# B163X.net
KiCad netlist of a schematic drawn in EAGLE
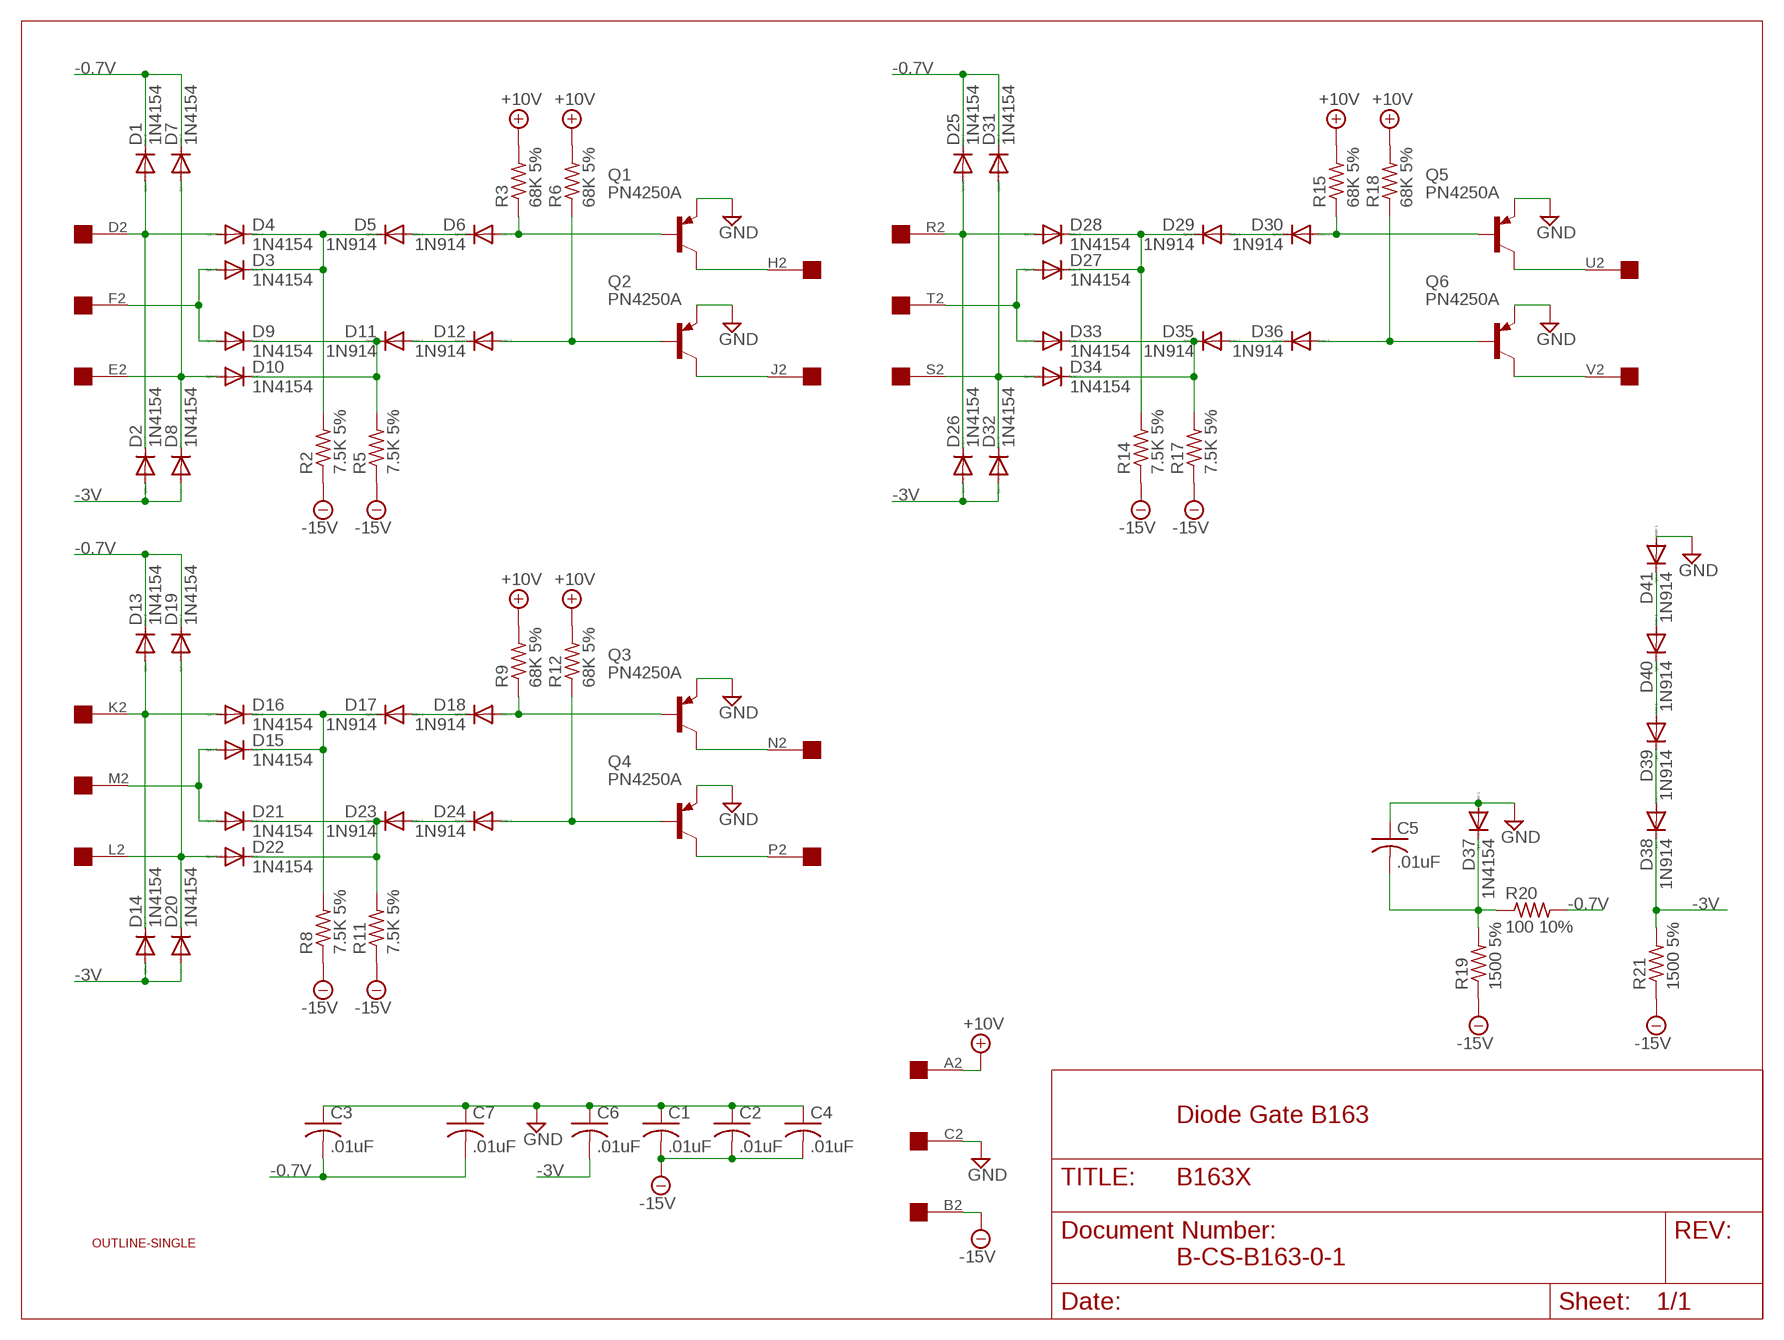
[diagram p0: schematic, sheet 1]

(export (version "E")
  (design (tool "Eeschema 10.0.6"))
  (components
    (comp (ref "C1")
      (value ".01uF")
      (footprint "eagle-import:C050-025X075")
      (libsource (lib "eagle-import") (part "C-US050-025X075"))
    )
    (comp (ref "C2")
      (value ".01uF")
      (footprint "eagle-import:C050-025X075")
      (libsource (lib "eagle-import") (part "C-US050-025X075"))
    )
    (comp (ref "C3")
      (value ".01uF")
      (footprint "eagle-import:C050-025X075")
      (libsource (lib "eagle-import") (part "C-US050-025X075"))
    )
    (comp (ref "C4")
      (value ".01uF")
      (footprint "eagle-import:C050-025X075")
      (libsource (lib "eagle-import") (part "C-US050-025X075"))
    )
    (comp (ref "C5")
      (value ".01uF")
      (footprint "eagle-import:C050-025X075")
      (libsource (lib "eagle-import") (part "C-US050-025X075"))
    )
    (comp (ref "C6")
      (value ".01uF")
      (footprint "eagle-import:C050-025X075")
      (libsource (lib "eagle-import") (part "C-US050-025X075"))
    )
    (comp (ref "C7")
      (value ".01uF")
      (footprint "eagle-import:C050-025X075")
      (libsource (lib "eagle-import") (part "C-US050-025X075"))
    )
    (comp (ref "D1")
      (value "1N4154")
      (footprint "eagle-import:DO35-10")
      (libsource (lib "eagle-import") (part "1N4148DO35-10"))
    )
    (comp (ref "D2")
      (value "1N4154")
      (footprint "eagle-import:DO35-10")
      (libsource (lib "eagle-import") (part "1N4148DO35-10"))
    )
    (comp (ref "D3")
      (value "1N4154")
      (footprint "eagle-import:DO35-10")
      (libsource (lib "eagle-import") (part "1N4148DO35-10"))
    )
    (comp (ref "D4")
      (value "1N4154")
      (footprint "eagle-import:DO35-10")
      (libsource (lib "eagle-import") (part "1N4148DO35-10"))
    )
    (comp (ref "D5")
      (value "1N914")
      (footprint "eagle-import:DO35-10")
      (libsource (lib "eagle-import") (part "1N4148DO35-10"))
    )
    (comp (ref "D6")
      (value "1N914")
      (footprint "eagle-import:DO35-10")
      (libsource (lib "eagle-import") (part "1N4148DO35-10"))
    )
    (comp (ref "D7")
      (value "1N4154")
      (footprint "eagle-import:DO35-10")
      (libsource (lib "eagle-import") (part "1N4148DO35-10"))
    )
    (comp (ref "D8")
      (value "1N4154")
      (footprint "eagle-import:DO35-10")
      (libsource (lib "eagle-import") (part "1N4148DO35-10"))
    )
    (comp (ref "D9")
      (value "1N4154")
      (footprint "eagle-import:DO35-10")
      (libsource (lib "eagle-import") (part "1N4148DO35-10"))
    )
    (comp (ref "D10")
      (value "1N4154")
      (footprint "eagle-import:DO35-10")
      (libsource (lib "eagle-import") (part "1N4148DO35-10"))
    )
    (comp (ref "D11")
      (value "1N914")
      (footprint "eagle-import:DO35-10")
      (libsource (lib "eagle-import") (part "1N4148DO35-10"))
    )
    (comp (ref "D12")
      (value "1N914")
      (footprint "eagle-import:DO35-10")
      (libsource (lib "eagle-import") (part "1N4148DO35-10"))
    )
    (comp (ref "D13")
      (value "1N4154")
      (footprint "eagle-import:DO35-10")
      (libsource (lib "eagle-import") (part "1N4148DO35-10"))
    )
    (comp (ref "D14")
      (value "1N4154")
      (footprint "eagle-import:DO35-10")
      (libsource (lib "eagle-import") (part "1N4148DO35-10"))
    )
    (comp (ref "D15")
      (value "1N4154")
      (footprint "eagle-import:DO35-10")
      (libsource (lib "eagle-import") (part "1N4148DO35-10"))
    )
    (comp (ref "D16")
      (value "1N4154")
      (footprint "eagle-import:DO35-10")
      (libsource (lib "eagle-import") (part "1N4148DO35-10"))
    )
    (comp (ref "D17")
      (value "1N914")
      (footprint "eagle-import:DO35-10")
      (libsource (lib "eagle-import") (part "1N4148DO35-10"))
    )
    (comp (ref "D18")
      (value "1N914")
      (footprint "eagle-import:DO35-10")
      (libsource (lib "eagle-import") (part "1N4148DO35-10"))
    )
    (comp (ref "D19")
      (value "1N4154")
      (footprint "eagle-import:DO35-10")
      (libsource (lib "eagle-import") (part "1N4148DO35-10"))
    )
    (comp (ref "D20")
      (value "1N4154")
      (footprint "eagle-import:DO35-10")
      (libsource (lib "eagle-import") (part "1N4148DO35-10"))
    )
    (comp (ref "D21")
      (value "1N4154")
      (footprint "eagle-import:DO35-10")
      (libsource (lib "eagle-import") (part "1N4148DO35-10"))
    )
    (comp (ref "D22")
      (value "1N4154")
      (footprint "eagle-import:DO35-10")
      (libsource (lib "eagle-import") (part "1N4148DO35-10"))
    )
    (comp (ref "D23")
      (value "1N914")
      (footprint "eagle-import:DO35-10")
      (libsource (lib "eagle-import") (part "1N4148DO35-10"))
    )
    (comp (ref "D24")
      (value "1N914")
      (footprint "eagle-import:DO35-10")
      (libsource (lib "eagle-import") (part "1N4148DO35-10"))
    )
    (comp (ref "D25")
      (value "1N4154")
      (footprint "eagle-import:DO35-10")
      (libsource (lib "eagle-import") (part "1N4148DO35-10"))
    )
    (comp (ref "D26")
      (value "1N4154")
      (footprint "eagle-import:DO35-10")
      (libsource (lib "eagle-import") (part "1N4148DO35-10"))
    )
    (comp (ref "D27")
      (value "1N4154")
      (footprint "eagle-import:DO35-10")
      (libsource (lib "eagle-import") (part "1N4148DO35-10"))
    )
    (comp (ref "D28")
      (value "1N4154")
      (footprint "eagle-import:DO35-10")
      (libsource (lib "eagle-import") (part "1N4148DO35-10"))
    )
    (comp (ref "D29")
      (value "1N914")
      (footprint "eagle-import:DO35-10")
      (libsource (lib "eagle-import") (part "1N4148DO35-10"))
    )
    (comp (ref "D30")
      (value "1N914")
      (footprint "eagle-import:DO35-10")
      (libsource (lib "eagle-import") (part "1N4148DO35-10"))
    )
    (comp (ref "D31")
      (value "1N4154")
      (footprint "eagle-import:DO35-10")
      (libsource (lib "eagle-import") (part "1N4148DO35-10"))
    )
    (comp (ref "D32")
      (value "1N4154")
      (footprint "eagle-import:DO35-10")
      (libsource (lib "eagle-import") (part "1N4148DO35-10"))
    )
    (comp (ref "D33")
      (value "1N4154")
      (footprint "eagle-import:DO35-10")
      (libsource (lib "eagle-import") (part "1N4148DO35-10"))
    )
    (comp (ref "D34")
      (value "1N4154")
      (footprint "eagle-import:DO35-10")
      (libsource (lib "eagle-import") (part "1N4148DO35-10"))
    )
    (comp (ref "D35")
      (value "1N914")
      (footprint "eagle-import:DO35-10")
      (libsource (lib "eagle-import") (part "1N4148DO35-10"))
    )
    (comp (ref "D36")
      (value "1N914")
      (footprint "eagle-import:DO35-10")
      (libsource (lib "eagle-import") (part "1N4148DO35-10"))
    )
    (comp (ref "D37")
      (value "1N4154")
      (footprint "eagle-import:DO35-10")
      (libsource (lib "eagle-import") (part "1N4148DO35-10"))
    )
    (comp (ref "D38")
      (value "1N914")
      (footprint "eagle-import:DO35-10")
      (libsource (lib "eagle-import") (part "1N4148DO35-10"))
    )
    (comp (ref "D39")
      (value "1N914")
      (footprint "eagle-import:DO35-10")
      (libsource (lib "eagle-import") (part "1N4148DO35-10"))
    )
    (comp (ref "D40")
      (value "1N914")
      (footprint "eagle-import:DO35-10")
      (libsource (lib "eagle-import") (part "1N4148DO35-10"))
    )
    (comp (ref "D41")
      (value "1N914")
      (footprint "eagle-import:DO35-10")
      (libsource (lib "eagle-import") (part "1N4148DO35-10"))
    )
    (comp (ref "Q1")
      (value "PN4250A")
      (footprint "eagle-import:TO39")
      (libsource (lib "eagle-import") (part "2N2904"))
    )
    (comp (ref "Q2")
      (value "PN4250A")
      (footprint "eagle-import:TO39")
      (libsource (lib "eagle-import") (part "2N2904"))
    )
    (comp (ref "Q3")
      (value "PN4250A")
      (footprint "eagle-import:TO39")
      (libsource (lib "eagle-import") (part "2N2904"))
    )
    (comp (ref "Q4")
      (value "PN4250A")
      (footprint "eagle-import:TO39")
      (libsource (lib "eagle-import") (part "2N2904"))
    )
    (comp (ref "Q5")
      (value "PN4250A")
      (footprint "eagle-import:TO39")
      (libsource (lib "eagle-import") (part "2N2904"))
    )
    (comp (ref "Q6")
      (value "PN4250A")
      (footprint "eagle-import:TO39")
      (libsource (lib "eagle-import") (part "2N2904"))
    )
    (comp (ref "R2")
      (value "7.5K 5%")
      (footprint "eagle-import:0207_10")
      (libsource (lib "eagle-import") (part "R-US_0207/10"))
    )
    (comp (ref "R3")
      (value "68K 5%")
      (footprint "eagle-import:0207_10")
      (libsource (lib "eagle-import") (part "R-US_0207/10"))
    )
    (comp (ref "R5")
      (value "7.5K 5%")
      (footprint "eagle-import:0207_10")
      (libsource (lib "eagle-import") (part "R-US_0207/10"))
    )
    (comp (ref "R6")
      (value "68K 5%")
      (footprint "eagle-import:0207_10")
      (libsource (lib "eagle-import") (part "R-US_0207/10"))
    )
    (comp (ref "R8")
      (value "7.5K 5%")
      (footprint "eagle-import:0207_10")
      (libsource (lib "eagle-import") (part "R-US_0207/10"))
    )
    (comp (ref "R9")
      (value "68K 5%")
      (footprint "eagle-import:0207_10")
      (libsource (lib "eagle-import") (part "R-US_0207/10"))
    )
    (comp (ref "R11")
      (value "7.5K 5%")
      (footprint "eagle-import:0207_10")
      (libsource (lib "eagle-import") (part "R-US_0207/10"))
    )
    (comp (ref "R12")
      (value "68K 5%")
      (footprint "eagle-import:0207_10")
      (libsource (lib "eagle-import") (part "R-US_0207/10"))
    )
    (comp (ref "R14")
      (value "7.5K 5%")
      (footprint "eagle-import:0207_10")
      (libsource (lib "eagle-import") (part "R-US_0207/10"))
    )
    (comp (ref "R15")
      (value "68K 5%")
      (footprint "eagle-import:0207_10")
      (libsource (lib "eagle-import") (part "R-US_0207/10"))
    )
    (comp (ref "R17")
      (value "7.5K 5%")
      (footprint "eagle-import:0207_10")
      (libsource (lib "eagle-import") (part "R-US_0207/10"))
    )
    (comp (ref "R18")
      (value "68K 5%")
      (footprint "eagle-import:0207_10")
      (libsource (lib "eagle-import") (part "R-US_0207/10"))
    )
    (comp (ref "R19")
      (value "1500 5%")
      (footprint "eagle-import:0207_10")
      (libsource (lib "eagle-import") (part "R-US_0207/10"))
    )
    (comp (ref "R20")
      (value "100 10%")
      (footprint "eagle-import:0207_10")
      (libsource (lib "eagle-import") (part "R-US_0207/10"))
    )
    (comp (ref "R21")
      (value "1500 5%")
      (footprint "eagle-import:0207_10")
      (libsource (lib "eagle-import") (part "R-US_0207/10"))
    )
    (comp (ref "U$1")
      (value "OUTLINE-SINGLE")
      (footprint "eagle-import:SINGLE")
      (libsource (lib "eagle-import") (part "OUTLINE-SINGLE"))
    )
    (comp (ref "U$2")
      (value "EDGE-1")
      (footprint "eagle-import:EDGE-CON1")
      (libsource (lib "eagle-import") (part "EDGE-1"))
    )
  )
  (nets
    (net (code "1") (name "+10V") (class "Default")
      (node (ref "R12") (pin "2") (pinfunction "2_2") (pintype "passive"))
      (node (ref "R15") (pin "2") (pinfunction "2_2") (pintype "passive"))
      (node (ref "R18") (pin "2") (pinfunction "2_2") (pintype "passive"))
      (node (ref "R3") (pin "2") (pinfunction "2_2") (pintype "passive"))
      (node (ref "R6") (pin "2") (pinfunction "2_2") (pintype "passive"))
      (node (ref "R9") (pin "2") (pinfunction "2_2") (pintype "passive"))
      (node (ref "U$2") (pin "A2") (pinfunction "1_A2") (pintype "bidirectional"))
    )
    (net (code "2") (name "-15V") (class "Default")
      (node (ref "C1") (pin "2") (pinfunction "2_2") (pintype "passive"))
      (node (ref "C2") (pin "2") (pinfunction "2_2") (pintype "passive"))
      (node (ref "C4") (pin "2") (pinfunction "2_2") (pintype "passive"))
      (node (ref "R11") (pin "1") (pinfunction "1_1") (pintype "passive"))
      (node (ref "R14") (pin "1") (pinfunction "1_1") (pintype "passive"))
      (node (ref "R17") (pin "1") (pinfunction "1_1") (pintype "passive"))
      (node (ref "R19") (pin "1") (pinfunction "1_1") (pintype "passive"))
      (node (ref "R2") (pin "1") (pinfunction "1_1") (pintype "passive"))
      (node (ref "R21") (pin "1") (pinfunction "1_1") (pintype "passive"))
      (node (ref "R5") (pin "1") (pinfunction "1_1") (pintype "passive"))
      (node (ref "R8") (pin "1") (pinfunction "1_1") (pintype "passive"))
      (node (ref "U$2") (pin "B2") (pinfunction "1_B2") (pintype "bidirectional"))
    )
    (net (code "3") (name "/-0.7V") (class "Default")
      (node (ref "C3") (pin "2") (pinfunction "2_2") (pintype "passive"))
      (node (ref "C7") (pin "2") (pinfunction "2_2") (pintype "passive"))
      (node (ref "D1") (pin "C") (pinfunction "C_C") (pintype "passive"))
      (node (ref "D13") (pin "C") (pinfunction "C_C") (pintype "passive"))
      (node (ref "D19") (pin "C") (pinfunction "C_C") (pintype "passive"))
      (node (ref "D25") (pin "C") (pinfunction "C_C") (pintype "passive"))
      (node (ref "D31") (pin "C") (pinfunction "C_C") (pintype "passive"))
      (node (ref "D7") (pin "C") (pinfunction "C_C") (pintype "passive"))
      (node (ref "R20") (pin "2") (pinfunction "2_2") (pintype "passive"))
    )
    (net (code "4") (name "/-3V") (class "Default")
      (node (ref "C6") (pin "2") (pinfunction "2_2") (pintype "passive"))
      (node (ref "D14") (pin "A") (pinfunction "A_A") (pintype "passive"))
      (node (ref "D2") (pin "A") (pinfunction "A_A") (pintype "passive"))
      (node (ref "D20") (pin "A") (pinfunction "A_A") (pintype "passive"))
      (node (ref "D26") (pin "A") (pinfunction "A_A") (pintype "passive"))
      (node (ref "D32") (pin "A") (pinfunction "A_A") (pintype "passive"))
      (node (ref "D38") (pin "C") (pinfunction "C_C") (pintype "passive"))
      (node (ref "D8") (pin "A") (pinfunction "A_A") (pintype "passive"))
      (node (ref "R21") (pin "2") (pinfunction "2_2") (pintype "passive"))
    )
    (net (code "5") (name "GND") (class "Default")
      (node (ref "C1") (pin "1") (pinfunction "1_1") (pintype "passive"))
      (node (ref "C2") (pin "1") (pinfunction "1_1") (pintype "passive"))
      (node (ref "C3") (pin "1") (pinfunction "1_1") (pintype "passive"))
      (node (ref "C4") (pin "1") (pinfunction "1_1") (pintype "passive"))
      (node (ref "C5") (pin "1") (pinfunction "1_1") (pintype "passive"))
      (node (ref "C6") (pin "1") (pinfunction "1_1") (pintype "passive"))
      (node (ref "C7") (pin "1") (pinfunction "1_1") (pintype "passive"))
      (node (ref "D37") (pin "A") (pinfunction "A_A") (pintype "passive"))
      (node (ref "D41") (pin "A") (pinfunction "A_A") (pintype "passive"))
      (node (ref "Q1") (pin "1") (pinfunction "E_1") (pintype "passive"))
      (node (ref "Q2") (pin "1") (pinfunction "E_1") (pintype "passive"))
      (node (ref "Q3") (pin "1") (pinfunction "E_1") (pintype "passive"))
      (node (ref "Q4") (pin "1") (pinfunction "E_1") (pintype "passive"))
      (node (ref "Q5") (pin "1") (pinfunction "E_1") (pintype "passive"))
      (node (ref "Q6") (pin "1") (pinfunction "E_1") (pintype "passive"))
      (node (ref "U$2") (pin "C2") (pinfunction "1_C2") (pintype "bidirectional"))
    )
    (net (code "6") (name "Net-(C5-Pad2)") (class "Default")
      (node (ref "C5") (pin "2") (pinfunction "2_2") (pintype "passive"))
      (node (ref "D37") (pin "C") (pinfunction "C_C") (pintype "passive"))
      (node (ref "R19") (pin "2") (pinfunction "2_2") (pintype "passive"))
      (node (ref "R20") (pin "1") (pinfunction "1_1") (pintype "passive"))
    )
    (net (code "7") (name "Net-(D3-PadC)") (class "Default")
      (node (ref "D3") (pin "C") (pinfunction "C_C") (pintype "passive"))
      (node (ref "D4") (pin "C") (pinfunction "C_C") (pintype "passive"))
      (node (ref "D5") (pin "C") (pinfunction "C_C") (pintype "passive"))
      (node (ref "R2") (pin "2") (pinfunction "2_2") (pintype "passive"))
    )
    (net (code "8") (name "Net-(D5-PadA)") (class "Default")
      (node (ref "D5") (pin "A") (pinfunction "A_A") (pintype "passive"))
      (node (ref "D6") (pin "C") (pinfunction "C_C") (pintype "passive"))
    )
    (net (code "9") (name "Net-(D10-PadC)") (class "Default")
      (node (ref "D10") (pin "C") (pinfunction "C_C") (pintype "passive"))
      (node (ref "D11") (pin "C") (pinfunction "C_C") (pintype "passive"))
      (node (ref "D9") (pin "C") (pinfunction "C_C") (pintype "passive"))
      (node (ref "R5") (pin "2") (pinfunction "2_2") (pintype "passive"))
    )
    (net (code "10") (name "Net-(D11-PadA)") (class "Default")
      (node (ref "D11") (pin "A") (pinfunction "A_A") (pintype "passive"))
      (node (ref "D12") (pin "C") (pinfunction "C_C") (pintype "passive"))
    )
    (net (code "11") (name "Net-(D15-PadC)") (class "Default")
      (node (ref "D15") (pin "C") (pinfunction "C_C") (pintype "passive"))
      (node (ref "D16") (pin "C") (pinfunction "C_C") (pintype "passive"))
      (node (ref "D17") (pin "C") (pinfunction "C_C") (pintype "passive"))
      (node (ref "R8") (pin "2") (pinfunction "2_2") (pintype "passive"))
    )
    (net (code "12") (name "Net-(D17-PadA)") (class "Default")
      (node (ref "D17") (pin "A") (pinfunction "A_A") (pintype "passive"))
      (node (ref "D18") (pin "C") (pinfunction "C_C") (pintype "passive"))
    )
    (net (code "13") (name "Net-(D21-PadC)") (class "Default")
      (node (ref "D21") (pin "C") (pinfunction "C_C") (pintype "passive"))
      (node (ref "D22") (pin "C") (pinfunction "C_C") (pintype "passive"))
      (node (ref "D23") (pin "C") (pinfunction "C_C") (pintype "passive"))
      (node (ref "R11") (pin "2") (pinfunction "2_2") (pintype "passive"))
    )
    (net (code "14") (name "Net-(D23-PadA)") (class "Default")
      (node (ref "D23") (pin "A") (pinfunction "A_A") (pintype "passive"))
      (node (ref "D24") (pin "C") (pinfunction "C_C") (pintype "passive"))
    )
    (net (code "15") (name "Net-(D27-PadC)") (class "Default")
      (node (ref "D27") (pin "C") (pinfunction "C_C") (pintype "passive"))
      (node (ref "D28") (pin "C") (pinfunction "C_C") (pintype "passive"))
      (node (ref "D29") (pin "C") (pinfunction "C_C") (pintype "passive"))
      (node (ref "R14") (pin "2") (pinfunction "2_2") (pintype "passive"))
    )
    (net (code "16") (name "Net-(D29-PadA)") (class "Default")
      (node (ref "D29") (pin "A") (pinfunction "A_A") (pintype "passive"))
      (node (ref "D30") (pin "C") (pinfunction "C_C") (pintype "passive"))
    )
    (net (code "17") (name "Net-(D33-PadC)") (class "Default")
      (node (ref "D33") (pin "C") (pinfunction "C_C") (pintype "passive"))
      (node (ref "D34") (pin "C") (pinfunction "C_C") (pintype "passive"))
      (node (ref "D35") (pin "C") (pinfunction "C_C") (pintype "passive"))
      (node (ref "R17") (pin "2") (pinfunction "2_2") (pintype "passive"))
    )
    (net (code "18") (name "Net-(D35-PadA)") (class "Default")
      (node (ref "D35") (pin "A") (pinfunction "A_A") (pintype "passive"))
      (node (ref "D36") (pin "C") (pinfunction "C_C") (pintype "passive"))
    )
    (net (code "19") (name "Net-(D38-PadA)") (class "Default")
      (node (ref "D38") (pin "A") (pinfunction "A_A") (pintype "passive"))
      (node (ref "D39") (pin "C") (pinfunction "C_C") (pintype "passive"))
    )
    (net (code "20") (name "Net-(D39-PadA)") (class "Default")
      (node (ref "D39") (pin "A") (pinfunction "A_A") (pintype "passive"))
      (node (ref "D40") (pin "C") (pinfunction "C_C") (pintype "passive"))
    )
    (net (code "21") (name "Net-(D40-PadA)") (class "Default")
      (node (ref "D40") (pin "A") (pinfunction "A_A") (pintype "passive"))
      (node (ref "D41") (pin "C") (pinfunction "C_C") (pintype "passive"))
    )
    (net (code "22") (name "Net-(Q1-B)") (class "Default")
      (node (ref "D6") (pin "A") (pinfunction "A_A") (pintype "passive"))
      (node (ref "Q1") (pin "2") (pinfunction "B_2") (pintype "passive"))
      (node (ref "R3") (pin "1") (pinfunction "1_1") (pintype "passive"))
    )
    (net (code "23") (name "Net-(Q1-C)") (class "Default")
      (node (ref "Q1") (pin "3") (pinfunction "C_3") (pintype "passive"))
      (node (ref "U$2") (pin "H2") (pinfunction "1_H2") (pintype "bidirectional"))
    )
    (net (code "24") (name "Net-(Q2-B)") (class "Default")
      (node (ref "D12") (pin "A") (pinfunction "A_A") (pintype "passive"))
      (node (ref "Q2") (pin "2") (pinfunction "B_2") (pintype "passive"))
      (node (ref "R6") (pin "1") (pinfunction "1_1") (pintype "passive"))
    )
    (net (code "25") (name "Net-(Q2-C)") (class "Default")
      (node (ref "Q2") (pin "3") (pinfunction "C_3") (pintype "passive"))
      (node (ref "U$2") (pin "J2") (pinfunction "1_J2") (pintype "bidirectional"))
    )
    (net (code "26") (name "Net-(Q3-B)") (class "Default")
      (node (ref "D18") (pin "A") (pinfunction "A_A") (pintype "passive"))
      (node (ref "Q3") (pin "2") (pinfunction "B_2") (pintype "passive"))
      (node (ref "R9") (pin "1") (pinfunction "1_1") (pintype "passive"))
    )
    (net (code "27") (name "Net-(Q3-C)") (class "Default")
      (node (ref "Q3") (pin "3") (pinfunction "C_3") (pintype "passive"))
      (node (ref "U$2") (pin "N2") (pinfunction "1_N2") (pintype "bidirectional"))
    )
    (net (code "28") (name "Net-(Q4-B)") (class "Default")
      (node (ref "D24") (pin "A") (pinfunction "A_A") (pintype "passive"))
      (node (ref "Q4") (pin "2") (pinfunction "B_2") (pintype "passive"))
      (node (ref "R12") (pin "1") (pinfunction "1_1") (pintype "passive"))
    )
    (net (code "29") (name "Net-(Q4-C)") (class "Default")
      (node (ref "Q4") (pin "3") (pinfunction "C_3") (pintype "passive"))
      (node (ref "U$2") (pin "P2") (pinfunction "1_P2") (pintype "bidirectional"))
    )
    (net (code "30") (name "Net-(Q5-B)") (class "Default")
      (node (ref "D30") (pin "A") (pinfunction "A_A") (pintype "passive"))
      (node (ref "Q5") (pin "2") (pinfunction "B_2") (pintype "passive"))
      (node (ref "R15") (pin "1") (pinfunction "1_1") (pintype "passive"))
    )
    (net (code "31") (name "Net-(Q5-C)") (class "Default")
      (node (ref "Q5") (pin "3") (pinfunction "C_3") (pintype "passive"))
      (node (ref "U$2") (pin "U2") (pinfunction "1_U2") (pintype "bidirectional"))
    )
    (net (code "32") (name "Net-(Q6-B)") (class "Default")
      (node (ref "D36") (pin "A") (pinfunction "A_A") (pintype "passive"))
      (node (ref "Q6") (pin "2") (pinfunction "B_2") (pintype "passive"))
      (node (ref "R18") (pin "1") (pinfunction "1_1") (pintype "passive"))
    )
    (net (code "33") (name "Net-(Q6-C)") (class "Default")
      (node (ref "Q6") (pin "3") (pinfunction "C_3") (pintype "passive"))
      (node (ref "U$2") (pin "V2") (pinfunction "1_V2") (pintype "bidirectional"))
    )
    (net (code "34") (name "Net-(U$2D-1)") (class "Default")
      (node (ref "D1") (pin "A") (pinfunction "A_A") (pintype "passive"))
      (node (ref "D2") (pin "C") (pinfunction "C_C") (pintype "passive"))
      (node (ref "D4") (pin "A") (pinfunction "A_A") (pintype "passive"))
      (node (ref "U$2") (pin "D2") (pinfunction "1_D2") (pintype "bidirectional"))
    )
    (net (code "35") (name "Net-(U$2E-1)") (class "Default")
      (node (ref "D10") (pin "A") (pinfunction "A_A") (pintype "passive"))
      (node (ref "D7") (pin "A") (pinfunction "A_A") (pintype "passive"))
      (node (ref "D8") (pin "C") (pinfunction "C_C") (pintype "passive"))
      (node (ref "U$2") (pin "E2") (pinfunction "1_E2") (pintype "bidirectional"))
    )
    (net (code "36") (name "Net-(U$2F-1)") (class "Default")
      (node (ref "D3") (pin "A") (pinfunction "A_A") (pintype "passive"))
      (node (ref "D9") (pin "A") (pinfunction "A_A") (pintype "passive"))
      (node (ref "U$2") (pin "F2") (pinfunction "1_F2") (pintype "bidirectional"))
    )
    (net (code "37") (name "Net-(U$2I-1)") (class "Default")
      (node (ref "D13") (pin "A") (pinfunction "A_A") (pintype "passive"))
      (node (ref "D14") (pin "C") (pinfunction "C_C") (pintype "passive"))
      (node (ref "D16") (pin "A") (pinfunction "A_A") (pintype "passive"))
      (node (ref "U$2") (pin "K2") (pinfunction "1_K2") (pintype "bidirectional"))
    )
    (net (code "38") (name "Net-(U$2J-1)") (class "Default")
      (node (ref "D19") (pin "A") (pinfunction "A_A") (pintype "passive"))
      (node (ref "D20") (pin "C") (pinfunction "C_C") (pintype "passive"))
      (node (ref "D22") (pin "A") (pinfunction "A_A") (pintype "passive"))
      (node (ref "U$2") (pin "L2") (pinfunction "1_L2") (pintype "bidirectional"))
    )
    (net (code "39") (name "Net-(U$2K-1)") (class "Default")
      (node (ref "D15") (pin "A") (pinfunction "A_A") (pintype "passive"))
      (node (ref "D21") (pin "A") (pinfunction "A_A") (pintype "passive"))
      (node (ref "U$2") (pin "M2") (pinfunction "1_M2") (pintype "bidirectional"))
    )
    (net (code "40") (name "Net-(U$2N-1)") (class "Default")
      (node (ref "D25") (pin "A") (pinfunction "A_A") (pintype "passive"))
      (node (ref "D26") (pin "C") (pinfunction "C_C") (pintype "passive"))
      (node (ref "D28") (pin "A") (pinfunction "A_A") (pintype "passive"))
      (node (ref "U$2") (pin "R2") (pinfunction "1_R2") (pintype "bidirectional"))
    )
    (net (code "41") (name "Net-(U$2O-1)") (class "Default")
      (node (ref "D31") (pin "A") (pinfunction "A_A") (pintype "passive"))
      (node (ref "D32") (pin "C") (pinfunction "C_C") (pintype "passive"))
      (node (ref "D34") (pin "A") (pinfunction "A_A") (pintype "passive"))
      (node (ref "U$2") (pin "S2") (pinfunction "1_S2") (pintype "bidirectional"))
    )
    (net (code "42") (name "Net-(U$2P-1)") (class "Default")
      (node (ref "D27") (pin "A") (pinfunction "A_A") (pintype "passive"))
      (node (ref "D33") (pin "A") (pinfunction "A_A") (pintype "passive"))
      (node (ref "U$2") (pin "T2") (pinfunction "1_T2") (pintype "bidirectional"))
    )
  )
)
